# RobotPatient_BMI270_v1_1_Apr2023.net
KiCad netlist of a schematic drawn in EAGLE
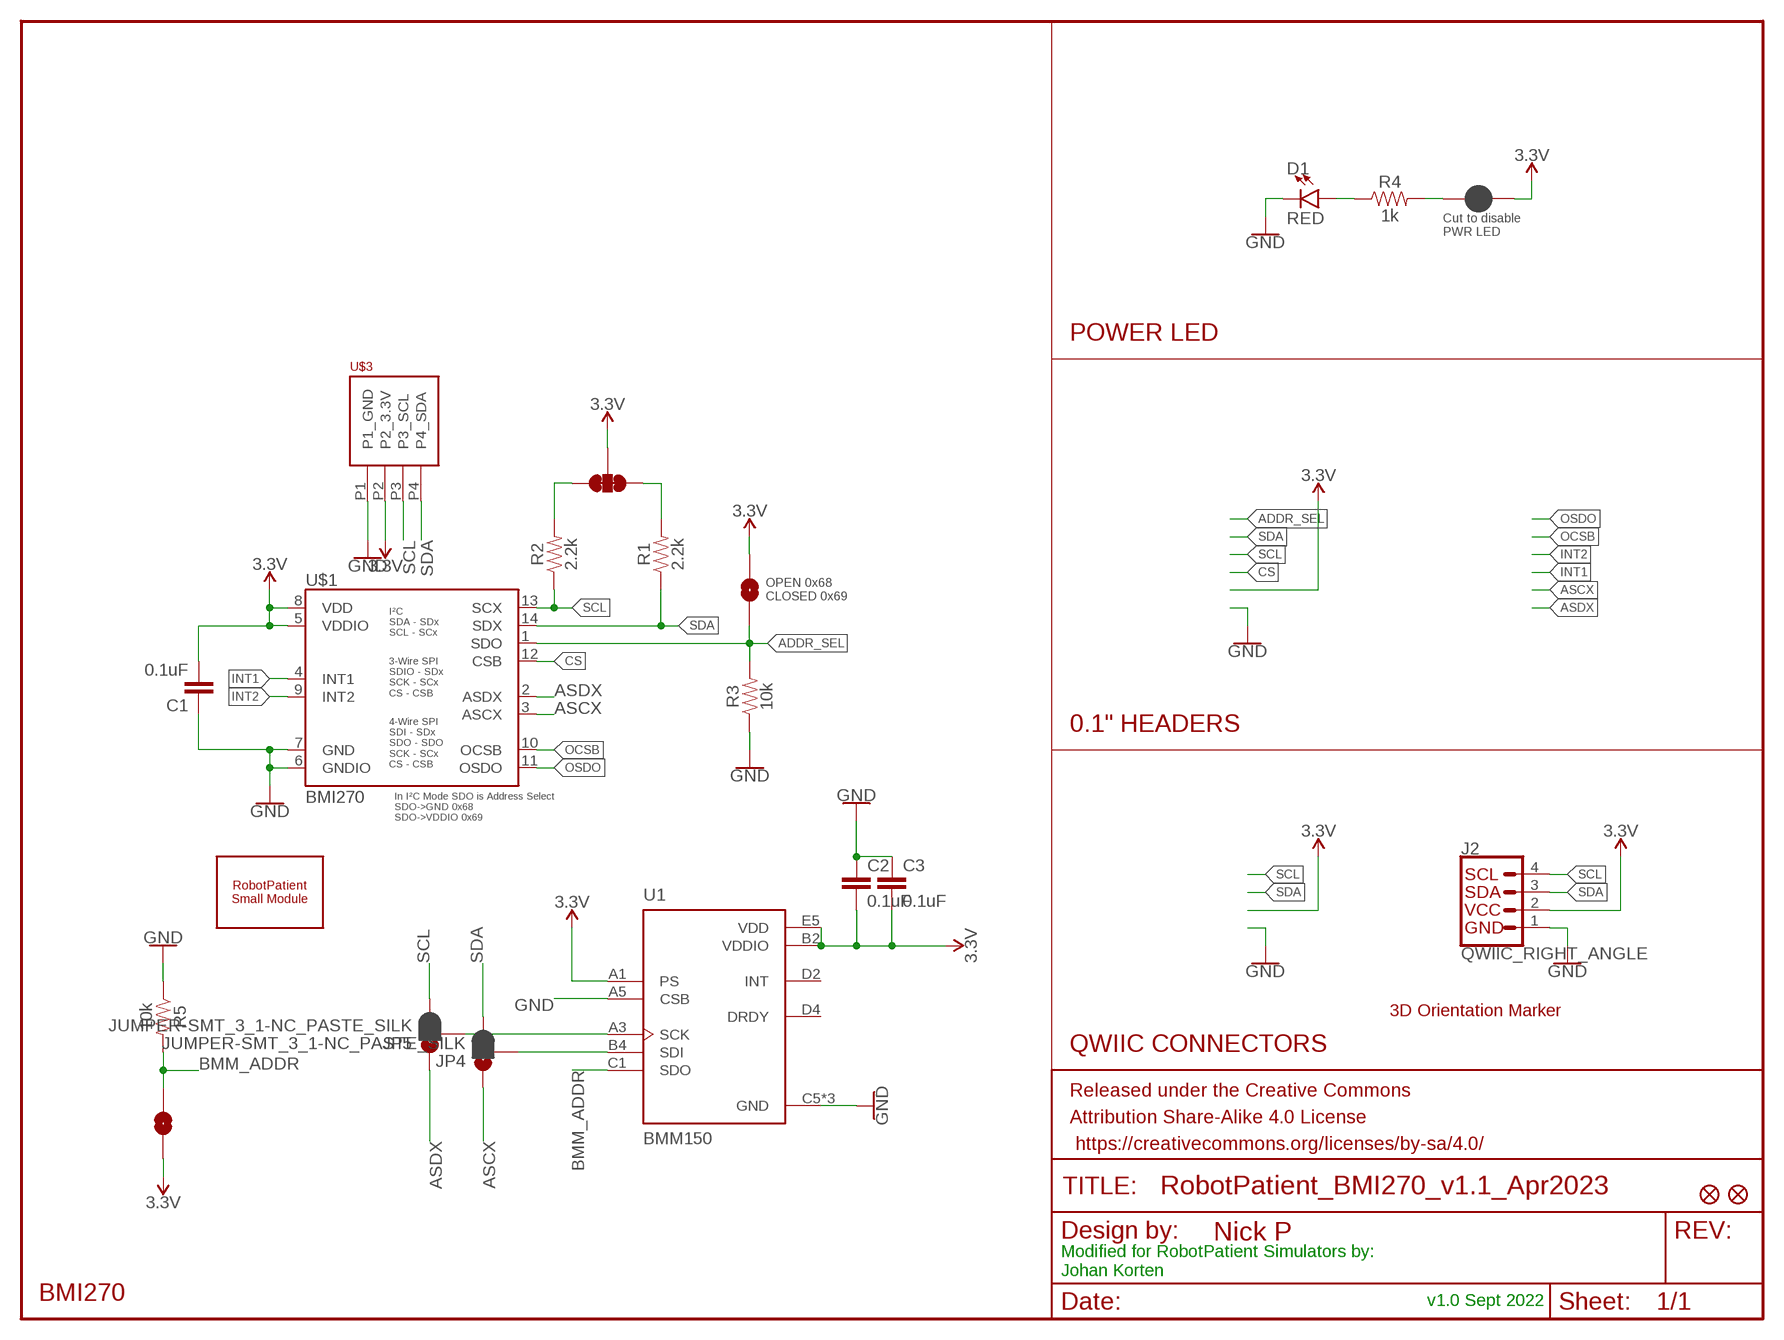
[diagram p0: schematic, sheet 1]

(export (version "E")
  (design (tool "Eeschema 10.0.6"))
  (components
    (comp (ref "C1")
      (value "0.1uF")
      (footprint "eagle-import:0603")
      (libsource (lib "eagle-import") (part "0.1UF-0603-25V-(+80/-20%)"))
    )
    (comp (ref "C2")
      (value "0.1uF")
      (footprint "eagle-import:0603")
      (libsource (lib "eagle-import") (part "SparkFun-Capacitors_510_0.1UF-0603-25V-(+80/-20%)"))
    )
    (comp (ref "C3")
      (value "0.1uF")
      (footprint "eagle-import:0603")
      (libsource (lib "eagle-import") (part "SparkFun-Capacitors_510_0.1UF-0603-25V-(+80/-20%)"))
    )
    (comp (ref "D1")
      (value "RED")
      (footprint "eagle-import:LED-0603")
      (libsource (lib "eagle-import") (part "LED-RED0603"))
    )
    (comp (ref "FD1")
      (value "FIDUCIAL1X2")
      (footprint "eagle-import:FIDUCIAL-1X2")
      (libsource (lib "eagle-import") (part "FIDUCIAL1X2"))
    )
    (comp (ref "FD2")
      (value "FIDUCIAL1X2")
      (footprint "eagle-import:FIDUCIAL-1X2")
      (libsource (lib "eagle-import") (part "FIDUCIAL1X2"))
    )
    (comp (ref "FRAME1")
      (value "FRAME-LETTERNO_PACKAGE")
      (footprint "eagle-import:DUMMY")
      (fields
        (field (name "DESIGNER") "Nick P")
        (field (name "VERSION") "1.0 Mar 23")
        (field (name "DESIGNER_1") "Nick P")
      )
      (libsource (lib "eagle-import") (part "FRAME-LETTERNO_PACKAGE"))
    )
    (comp (ref "J2")
      (value "QWIIC_RIGHT_ANGLE")
      (footprint "eagle-import:JST04_1MM_RA")
      (libsource (lib "eagle-import") (part "QWIIC_CONNECTORJS-1MM"))
    )
    (comp (ref "JP1")
      (value "JUMPER-SMT_3_2-NC_TRACE_SILK")
      (footprint "eagle-import:SMT-JUMPER_3_2-NC_TRACE_SILK")
      (libsource (lib "eagle-import") (part "JUMPER-SMT_3_2-NC_TRACE_SILK"))
    )
    (comp (ref "JP2")
      (value "JUMPER-SMT_2_NO_SILK")
      (footprint "eagle-import:SMT-JUMPER_2_NO_SILK")
      (libsource (lib "eagle-import") (part "JUMPER-SMT_2_NO_SILK"))
    )
    (comp (ref "JP3")
      (value "JUMPER-SMT_2_NC_PASTE_SILK")
      (footprint "eagle-import:SMT-JUMPER_2_NC_PASTE_SILK")
      (libsource (lib "eagle-import") (part "JUMPER-SMT_2_NC_PASTE_SILK"))
    )
    (comp (ref "JP4")
      (value "JUMPER-SMT_3_1-NC_PASTE_SILK")
      (footprint "eagle-import:SMT-JUMPER_3_1-NC_PASTE_SILK")
      (libsource (lib "eagle-import") (part "JUMPER-SMT_3_1-NC_PASTE_SILK"))
    )
    (comp (ref "JP5")
      (value "JUMPER-SMT_3_1-NC_PASTE_SILK")
      (footprint "eagle-import:SMT-JUMPER_3_1-NC_PASTE_SILK")
      (libsource (lib "eagle-import") (part "JUMPER-SMT_3_1-NC_PASTE_SILK"))
    )
    (comp (ref "JP6")
      (value "JUMPER-SMT_2_NO_SILK")
      (footprint "eagle-import:SMT-JUMPER_2_NO_SILK")
      (libsource (lib "eagle-import") (part "JUMPER-SMT_2_NO_SILK"))
    )
    (comp (ref "R1")
      (value "2.2k")
      (footprint "eagle-import:0603")
      (libsource (lib "eagle-import") (part "2.2KOHM-0603-1/10W-1%"))
    )
    (comp (ref "R2")
      (value "2.2k")
      (footprint "eagle-import:0603")
      (libsource (lib "eagle-import") (part "2.2KOHM-0603-1/10W-1%"))
    )
    (comp (ref "R3")
      (value "10k")
      (footprint "eagle-import:0603")
      (libsource (lib "eagle-import") (part "10KOHM-0603-1/10W-1%"))
    )
    (comp (ref "R4")
      (value "1k")
      (footprint "eagle-import:0603")
      (libsource (lib "eagle-import") (part "1KOHM-0603-1/10W-1%"))
    )
    (comp (ref "R5")
      (value "10k")
      (footprint "eagle-import:0603")
      (libsource (lib "eagle-import") (part "10KOHM-0603-1/10W-1%"))
    )
    (comp (ref "U$1")
      (value "BMI270")
      (footprint "eagle-import:BMI270")
      (libsource (lib "eagle-import") (part "BMI270"))
    )
    (comp (ref "U$2")
      (value "3D_MARKER")
      (footprint "eagle-import:3D_MARKER")
      (libsource (lib "eagle-import") (part "3D_MARKER"))
    )
    (comp (ref "U$3")
      (value "PHOENIX_PTSM_M4_THANGLE")
      (footprint "eagle-import:PTSM_M4_TH")
      (libsource (lib "eagle-import") (part "PHOENIX_PTSM_M4_THANGLE"))
    )
    (comp (ref "U$40")
      (value "ROBOTPATIENT_SMALL_MODULEBOARD")
      (footprint "eagle-import:RP_SMALL_SENSOR_OUTLINE")
      (libsource (lib "eagle-import") (part "ROBOTPATIENT_SMALL_MODULEBOARD"))
    )
    (comp (ref "U1")
      (value "BMM150")
      (footprint "eagle-import:XDCR_BMM150")
      (fields (field (name "MF") "Bosch Sensortec"))
      (libsource (lib "eagle-import") (part "BMM150"))
    )
  )
  (nets
    (net (code "1") (name "/BMM_ADDR") (class "Default")
      (node (ref "JP6") (pin "1") (pinfunction "1_1") (pintype "passive"))
      (node (ref "R5") (pin "2") (pinfunction "2_2") (pintype "passive"))
      (node (ref "U1") (pin "C1") (pinfunction "SDO_C1") (pintype "output"))
    )
    (net (code "2") (name "3.3V") (class "Default")
      (node (ref "C1") (pin "2") (pinfunction "2_2") (pintype "passive"))
      (node (ref "C2") (pin "2") (pinfunction "2_2") (pintype "passive"))
      (node (ref "C3") (pin "2") (pinfunction "2_2") (pintype "passive"))
      (node (ref "J2") (pin "2") (pinfunction "2_2") (pintype "power_in"))
      (node (ref "JP1") (pin "2") (pinfunction "2_2") (pintype "passive"))
      (node (ref "JP2") (pin "2") (pinfunction "2_2") (pintype "passive"))
      (node (ref "JP3") (pin "2") (pinfunction "2_2") (pintype "passive"))
      (node (ref "JP6") (pin "2") (pinfunction "2_2") (pintype "passive"))
      (node (ref "U$1") (pin "5") (pinfunction "VDDIO_5") (pintype "bidirectional"))
      (node (ref "U$1") (pin "8") (pinfunction "VDD_8") (pintype "bidirectional"))
      (node (ref "U$3") (pin "P2") (pinfunction "P2_3.3V_P2") (pintype "power_in"))
      (node (ref "U1") (pin "A1") (pinfunction "PS_A1") (pintype "input"))
      (node (ref "U1") (pin "B2") (pinfunction "VDDIO_B2") (pintype "power_in"))
      (node (ref "U1") (pin "E5") (pinfunction "VDD_E5") (pintype "power_in"))
    )
    (net (code "3") (name "ADDR_SEL") (class "Default")
      (node (ref "JP2") (pin "1") (pinfunction "1_1") (pintype "passive"))
      (node (ref "R3") (pin "2") (pinfunction "2_2") (pintype "passive"))
      (node (ref "U$1") (pin "1") (pinfunction "SDO_1") (pintype "bidirectional"))
    )
    (net (code "4") (name "ASCX") (class "Default")
      (node (ref "JP4") (pin "1") (pinfunction "1_1") (pintype "passive"))
      (node (ref "U$1") (pin "3") (pinfunction "ASCX_3") (pintype "bidirectional"))
    )
    (net (code "5") (name "ASDX") (class "Default")
      (node (ref "JP5") (pin "1") (pinfunction "1_1") (pintype "passive"))
      (node (ref "U$1") (pin "2") (pinfunction "ASDX_2") (pintype "bidirectional"))
    )
    (net (code "6") (name "CS") (class "Default")
      (node (ref "U$1") (pin "12") (pinfunction "CSB_12") (pintype "bidirectional"))
    )
    (net (code "7") (name "GND") (class "Default")
      (node (ref "C1") (pin "1") (pinfunction "1_1") (pintype "passive"))
      (node (ref "C2") (pin "1") (pinfunction "1_1") (pintype "passive"))
      (node (ref "C3") (pin "1") (pinfunction "1_1") (pintype "passive"))
      (node (ref "D1") (pin "C") (pinfunction "C_C") (pintype "passive"))
      (node (ref "J2") (pin "1") (pinfunction "1_1") (pintype "power_in"))
      (node (ref "R3") (pin "1") (pinfunction "1_1") (pintype "passive"))
      (node (ref "R5") (pin "1") (pinfunction "1_1") (pintype "passive"))
      (node (ref "U$1") (pin "6") (pinfunction "GNDIO_6") (pintype "bidirectional"))
      (node (ref "U$1") (pin "7") (pinfunction "GND_7") (pintype "bidirectional"))
      (node (ref "U$3") (pin "P1") (pinfunction "P1_GND_P1") (pintype "power_in"))
      (node (ref "U1") (pin "A5") (pinfunction "CSB_A5") (pintype "input"))
      (node (ref "U1") (pin "C5") (pinfunction "GND_C5") (pintype "power_in"))
      (node (ref "U1") (pin "E1") (pinfunction "GND_E1") (pintype "power_in"))
      (node (ref "U1") (pin "E3") (pinfunction "GND_E3") (pintype "power_in"))
    )
    (net (code "8") (name "INT1") (class "Default")
      (node (ref "U$1") (pin "4") (pinfunction "INT1_4") (pintype "bidirectional"))
    )
    (net (code "9") (name "INT2") (class "Default")
      (node (ref "U$1") (pin "9") (pinfunction "INT2_9") (pintype "bidirectional"))
    )
    (net (code "10") (name "Net-(D1-PadA)") (class "Default")
      (node (ref "D1") (pin "A") (pinfunction "A_A") (pintype "passive"))
      (node (ref "R4") (pin "1") (pinfunction "1_1") (pintype "passive"))
    )
    (net (code "11") (name "Net-(JP1-Pad1)") (class "Default")
      (node (ref "JP1") (pin "1") (pinfunction "1_1") (pintype "passive"))
      (node (ref "R1") (pin "2") (pinfunction "2_2") (pintype "passive"))
    )
    (net (code "12") (name "Net-(JP1-Pad3)") (class "Default")
      (node (ref "JP1") (pin "3") (pinfunction "3_3") (pintype "passive"))
      (node (ref "R2") (pin "2") (pinfunction "2_2") (pintype "passive"))
    )
    (net (code "13") (name "Net-(JP3-Pad1)") (class "Default")
      (node (ref "JP3") (pin "1") (pinfunction "1_1") (pintype "passive"))
      (node (ref "R4") (pin "2") (pinfunction "2_2") (pintype "passive"))
    )
    (net (code "14") (name "Net-(U1-SCK)") (class "Default")
      (node (ref "JP5") (pin "2") (pinfunction "2_2") (pintype "passive"))
      (node (ref "U1") (pin "A3") (pinfunction "SCK_A3") (pintype "input"))
    )
    (net (code "15") (name "Net-(U1-SDI)") (class "Default")
      (node (ref "JP4") (pin "2") (pinfunction "2_2") (pintype "passive"))
      (node (ref "U1") (pin "B4") (pinfunction "SDI_B4") (pintype "bidirectional"))
    )
    (net (code "16") (name "OCSB") (class "Default")
      (node (ref "U$1") (pin "10") (pinfunction "OCSB_10") (pintype "bidirectional"))
    )
    (net (code "17") (name "OSDO") (class "Default")
      (node (ref "U$1") (pin "11") (pinfunction "OSDO_11") (pintype "bidirectional"))
    )
    (net (code "18") (name "SCL") (class "Default")
      (node (ref "J2") (pin "4") (pinfunction "4_4") (pintype "passive"))
      (node (ref "JP5") (pin "3") (pinfunction "3_3") (pintype "passive"))
      (node (ref "R2") (pin "1") (pinfunction "1_1") (pintype "passive"))
      (node (ref "U$1") (pin "13") (pinfunction "SCX_13") (pintype "bidirectional"))
      (node (ref "U$3") (pin "P3") (pinfunction "P3_SCL_P3") (pintype "bidirectional"))
    )
    (net (code "19") (name "SDA") (class "Default")
      (node (ref "J2") (pin "3") (pinfunction "3_3") (pintype "passive"))
      (node (ref "JP4") (pin "3") (pinfunction "3_3") (pintype "passive"))
      (node (ref "R1") (pin "1") (pinfunction "1_1") (pintype "passive"))
      (node (ref "U$1") (pin "14") (pinfunction "SDX_14") (pintype "bidirectional"))
      (node (ref "U$3") (pin "P4") (pinfunction "P4_SDA_P4") (pintype "bidirectional"))
    )
    (net (code "20") (name "unconnected-(U1-DRDY-PadD4)") (class "Default")
      (node (ref "U1") (pin "D4") (pinfunction "DRDY_D4") (pintype "output"))
    )
    (net (code "21") (name "unconnected-(U1-INT-PadD2)") (class "Default")
      (node (ref "U1") (pin "D2") (pinfunction "INT_D2") (pintype "output"))
    )
  )
)
